# ImageSignalProcessor.net
KiCad netlist of a schematic drawn in Altium Designer
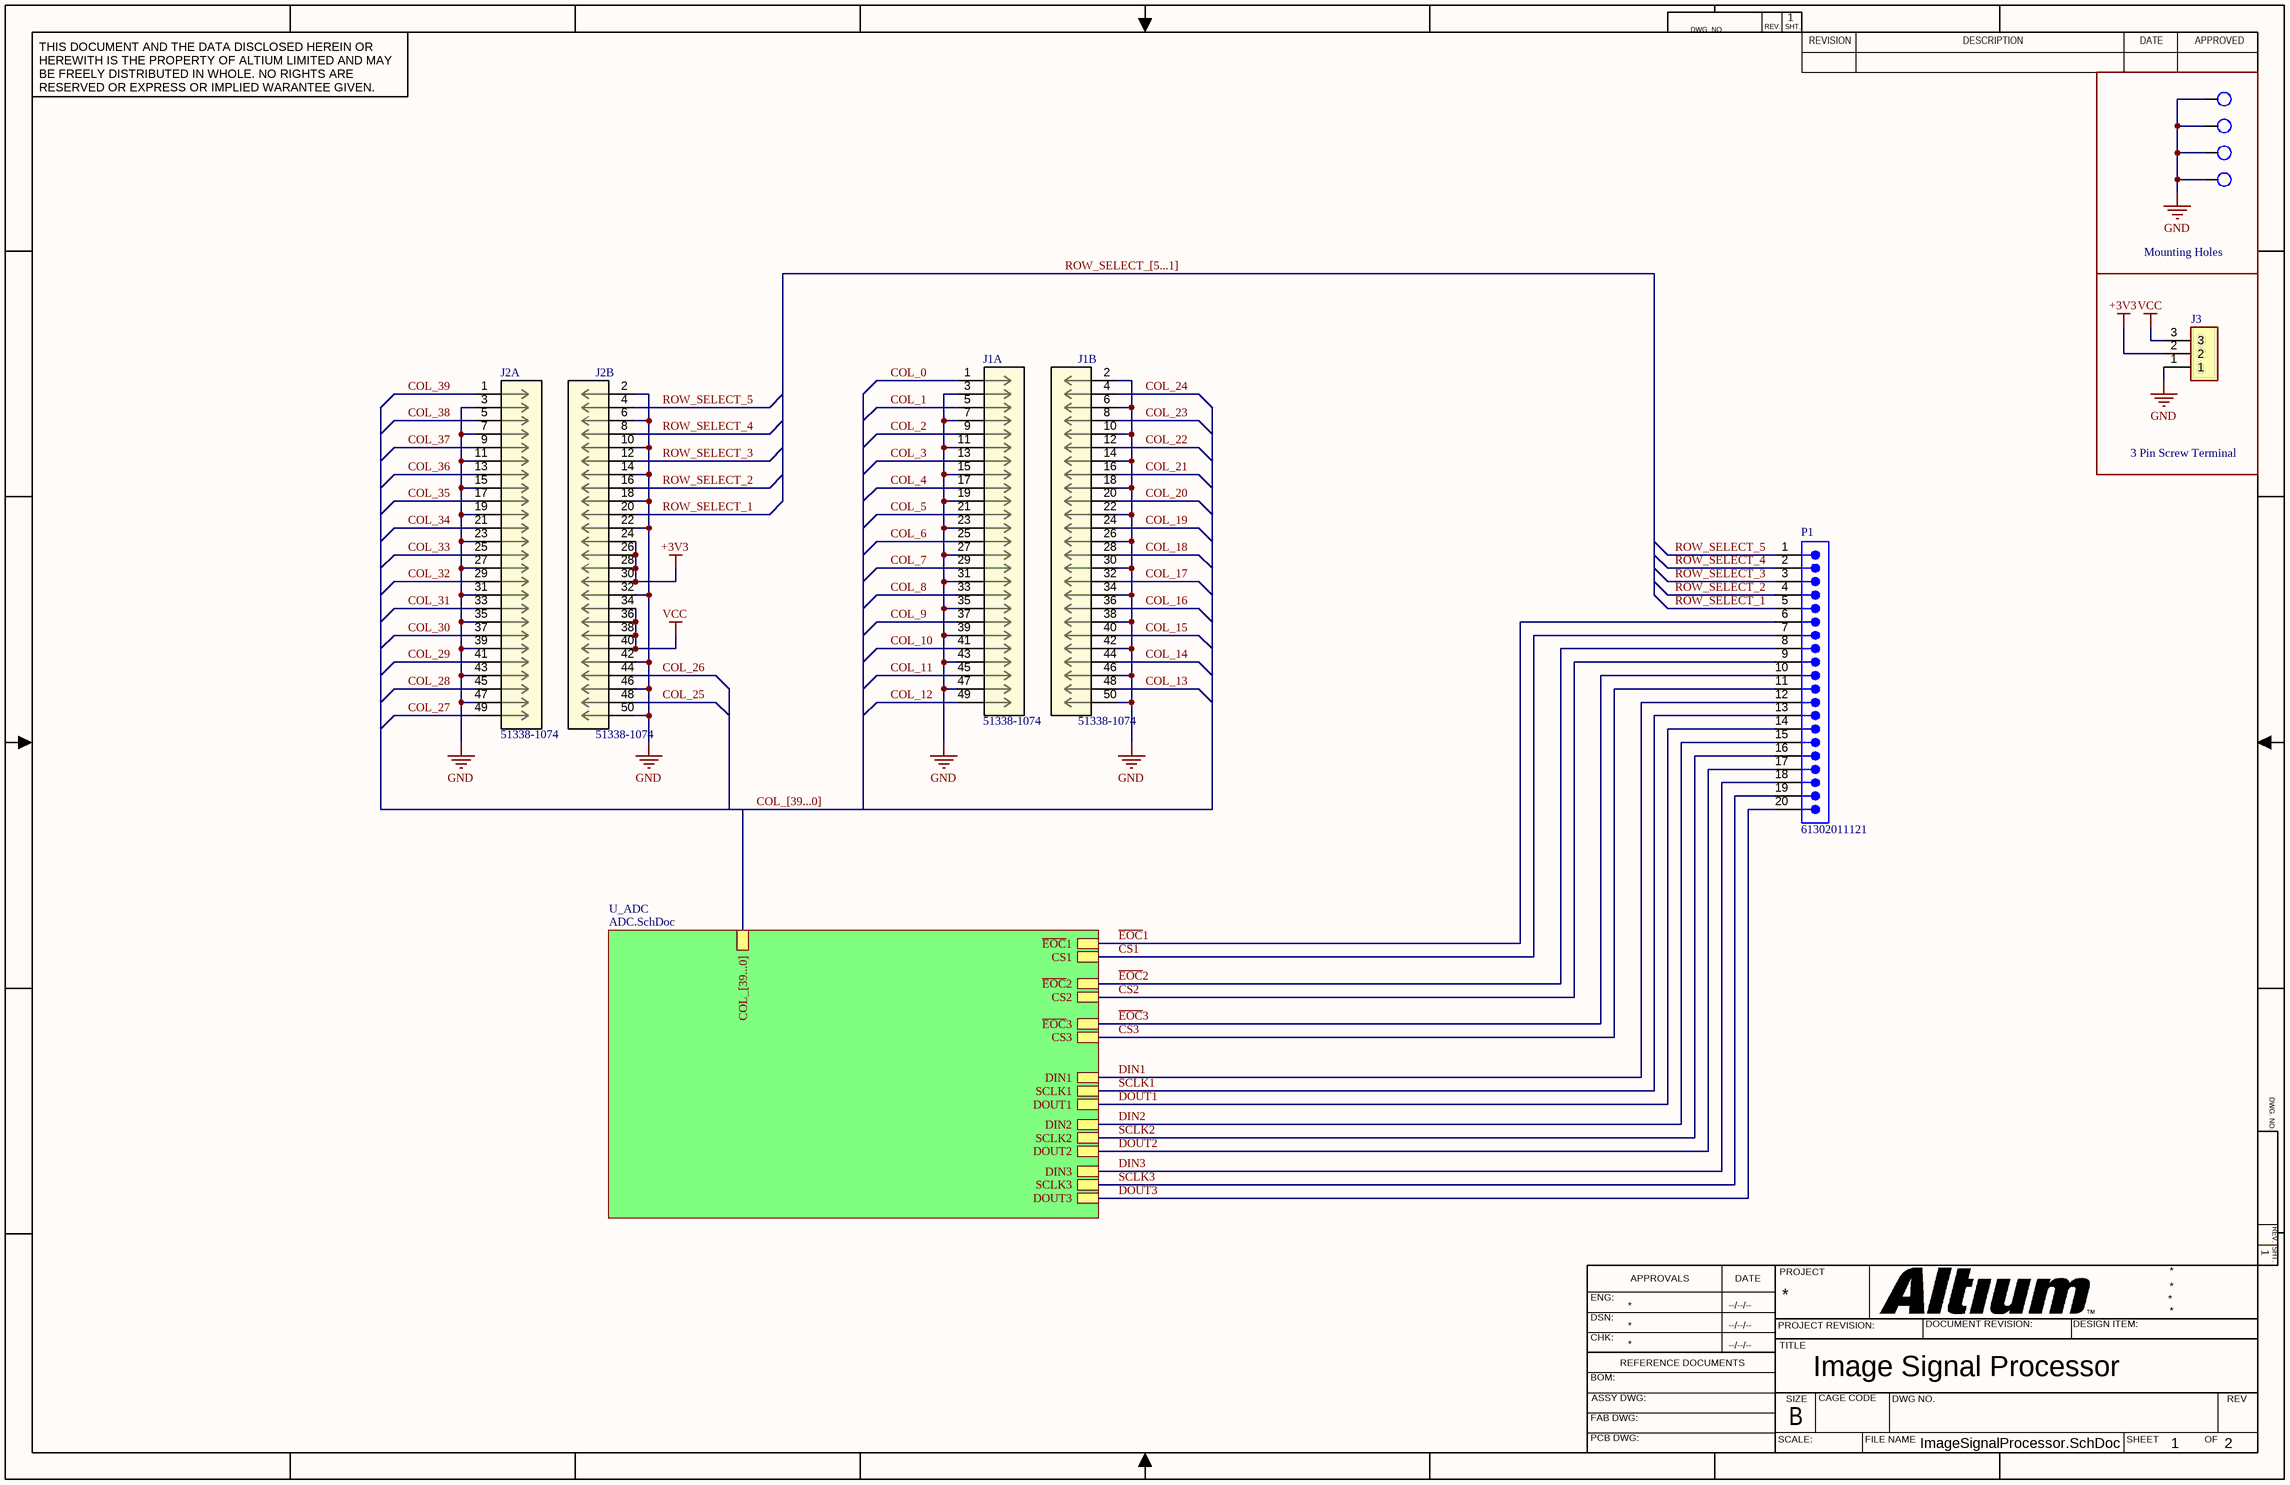
[diagram p0: ImageSignalProcessor.SchDoc]

(export (version "E")
  (design (tool "Eeschema 10.0.6"))
  (components
    (comp (ref "J1")
      (value "51338-1074")
      (footprint "51338-1074")
      (fields (field (name "MANUFACTURER") "Molex"))
      (libsource (lib "NeoObscura") (part "51338-1074"))
    )
    (comp (ref "J2")
      (value "51338-1074")
      (footprint "51338-1074")
      (fields (field (name "MANUFACTURER") "Molex"))
      (libsource (lib "NeoObscura") (part "51338-1074"))
    )
    (comp (ref "J3")
      (value "3 Pin Screw Terminal")
      (footprint "TE_282837-3")
      (description "Modular Terminal Block, 13.5A, 1.5mm2, 1 Row(s), 1 Deck(s)")
      (fields
        (field (name "MANUFACTURER") "TE Connectivity")
        (field (name "MANUFACTURER PART NUMBER") "282837-3")
        (field (name "SAFETY APPROVAL") "UL")
      )
      (libsource (lib "NeoObscura") (part "282837-3"))
    )
    (comp (ref "MP1")
      (value "M3 MOUNTING HOLE")
      (footprint "M3 MOUNTING HOLE")
      (libsource (lib "NeoObscura") (part "M3 MOUNTING HOLE"))
    )
    (comp (ref "MP2")
      (value "M3 MOUNTING HOLE")
      (footprint "M3 MOUNTING HOLE")
      (libsource (lib "NeoObscura") (part "M3 MOUNTING HOLE"))
    )
    (comp (ref "MP3")
      (value "M3 MOUNTING HOLE")
      (footprint "M3 MOUNTING HOLE")
      (libsource (lib "NeoObscura") (part "M3 MOUNTING HOLE"))
    )
    (comp (ref "MP4")
      (value "M3 MOUNTING HOLE")
      (footprint "M3 MOUNTING HOLE")
      (libsource (lib "NeoObscura") (part "M3 MOUNTING HOLE"))
    )
    (comp (ref "P1")
      (value "61302011121")
      (footprint "61302011121")
      (libsource (lib "Altium Content Vault") (part "Header_Male_1R_20P"))
    )
  )
  (nets
    (net (code "3") (name "+3V3") (class "Default")
      (node (ref "J2") (pin "24") (pinfunction "24_24") (pintype "passive"))
      (node (ref "J2") (pin "26") (pinfunction "26_26") (pintype "passive"))
      (node (ref "J2") (pin "28") (pinfunction "28_28") (pintype "passive"))
      (node (ref "J2") (pin "30") (pinfunction "30_30") (pintype "passive"))
      (node (ref "J3") (pin "2") (pinfunction "2_2") (pintype "passive"))
    )
    (net (code "4") (name "/COL_0") (class "Default")
      (node (ref "J1") (pin "1") (pinfunction "1_1") (pintype "passive"))
    )
    (net (code "5") (name "/COL_1") (class "Default")
      (node (ref "J1") (pin "5") (pinfunction "5_5") (pintype "passive"))
    )
    (net (code "6") (name "/COL_2") (class "Default")
      (node (ref "J1") (pin "9") (pinfunction "9_9") (pintype "passive"))
    )
    (net (code "7") (name "/COL_3") (class "Default")
      (node (ref "J1") (pin "13") (pinfunction "13_13") (pintype "passive"))
    )
    (net (code "8") (name "/COL_4") (class "Default")
      (node (ref "J1") (pin "17") (pinfunction "17_17") (pintype "passive"))
    )
    (net (code "9") (name "/COL_5") (class "Default")
      (node (ref "J1") (pin "21") (pinfunction "21_21") (pintype "passive"))
    )
    (net (code "10") (name "/COL_6") (class "Default")
      (node (ref "J1") (pin "25") (pinfunction "25_25") (pintype "passive"))
    )
    (net (code "11") (name "/COL_7") (class "Default")
      (node (ref "J1") (pin "29") (pinfunction "29_29") (pintype "passive"))
    )
    (net (code "12") (name "/COL_8") (class "Default")
      (node (ref "J1") (pin "33") (pinfunction "33_33") (pintype "passive"))
    )
    (net (code "13") (name "/COL_9") (class "Default")
      (node (ref "J1") (pin "37") (pinfunction "37_37") (pintype "passive"))
    )
    (net (code "14") (name "/COL_10") (class "Default")
      (node (ref "J1") (pin "41") (pinfunction "41_41") (pintype "passive"))
    )
    (net (code "15") (name "/COL_11") (class "Default")
      (node (ref "J1") (pin "45") (pinfunction "45_45") (pintype "passive"))
    )
    (net (code "16") (name "/COL_12") (class "Default")
      (node (ref "J1") (pin "49") (pinfunction "49_49") (pintype "passive"))
    )
    (net (code "17") (name "/COL_13") (class "Default")
      (node (ref "J1") (pin "48") (pinfunction "48_48") (pintype "passive"))
    )
    (net (code "18") (name "/COL_14") (class "Default")
      (node (ref "J1") (pin "44") (pinfunction "44_44") (pintype "passive"))
    )
    (net (code "19") (name "/COL_15") (class "Default")
      (node (ref "J1") (pin "40") (pinfunction "40_40") (pintype "passive"))
    )
    (net (code "20") (name "/COL_16") (class "Default")
      (node (ref "J1") (pin "36") (pinfunction "36_36") (pintype "passive"))
    )
    (net (code "21") (name "/COL_17") (class "Default")
      (node (ref "J1") (pin "32") (pinfunction "32_32") (pintype "passive"))
    )
    (net (code "22") (name "/COL_18") (class "Default")
      (node (ref "J1") (pin "28") (pinfunction "28_28") (pintype "passive"))
    )
    (net (code "23") (name "/COL_19") (class "Default")
      (node (ref "J1") (pin "24") (pinfunction "24_24") (pintype "passive"))
    )
    (net (code "24") (name "/COL_20") (class "Default")
      (node (ref "J1") (pin "20") (pinfunction "20_20") (pintype "passive"))
    )
    (net (code "25") (name "/COL_21") (class "Default")
      (node (ref "J1") (pin "16") (pinfunction "16_16") (pintype "passive"))
    )
    (net (code "26") (name "/COL_22") (class "Default")
      (node (ref "J1") (pin "12") (pinfunction "12_12") (pintype "passive"))
    )
    (net (code "27") (name "/COL_23") (class "Default")
      (node (ref "J1") (pin "8") (pinfunction "8_8") (pintype "passive"))
    )
    (net (code "28") (name "/COL_24") (class "Default")
      (node (ref "J1") (pin "4") (pinfunction "4_4") (pintype "passive"))
    )
    (net (code "29") (name "/COL_25") (class "Default")
      (node (ref "J2") (pin "48") (pinfunction "48_48") (pintype "passive"))
    )
    (net (code "30") (name "/COL_26") (class "Default")
      (node (ref "J2") (pin "44") (pinfunction "44_44") (pintype "passive"))
    )
    (net (code "31") (name "/COL_27") (class "Default")
      (node (ref "J2") (pin "49") (pinfunction "49_49") (pintype "passive"))
    )
    (net (code "32") (name "/COL_28") (class "Default")
      (node (ref "J2") (pin "45") (pinfunction "45_45") (pintype "passive"))
    )
    (net (code "33") (name "/COL_29") (class "Default")
      (node (ref "J2") (pin "41") (pinfunction "41_41") (pintype "passive"))
    )
    (net (code "34") (name "/COL_30") (class "Default")
      (node (ref "J2") (pin "37") (pinfunction "37_37") (pintype "passive"))
    )
    (net (code "35") (name "/COL_31") (class "Default")
      (node (ref "J2") (pin "33") (pinfunction "33_33") (pintype "passive"))
    )
    (net (code "36") (name "/COL_32") (class "Default")
      (node (ref "J2") (pin "29") (pinfunction "29_29") (pintype "passive"))
    )
    (net (code "37") (name "/COL_33") (class "Default")
      (node (ref "J2") (pin "25") (pinfunction "25_25") (pintype "passive"))
    )
    (net (code "38") (name "/COL_34") (class "Default")
      (node (ref "J2") (pin "21") (pinfunction "21_21") (pintype "passive"))
    )
    (net (code "39") (name "/COL_35") (class "Default")
      (node (ref "J2") (pin "17") (pinfunction "17_17") (pintype "passive"))
    )
    (net (code "40") (name "/COL_36") (class "Default")
      (node (ref "J2") (pin "13") (pinfunction "13_13") (pintype "passive"))
    )
    (net (code "41") (name "/COL_37") (class "Default")
      (node (ref "J2") (pin "9") (pinfunction "9_9") (pintype "passive"))
    )
    (net (code "42") (name "/COL_38") (class "Default")
      (node (ref "J2") (pin "5") (pinfunction "5_5") (pintype "passive"))
    )
    (net (code "43") (name "/COL_39") (class "Default")
      (node (ref "J2") (pin "1") (pinfunction "1_1") (pintype "passive"))
    )
    (net (code "44") (name "/CS1") (class "Default")
      (node (ref "P1") (pin "7") (pinfunction "7_7") (pintype "passive"))
    )
    (net (code "45") (name "/CS2") (class "Default")
      (node (ref "P1") (pin "9") (pinfunction "9_9") (pintype "passive"))
    )
    (net (code "46") (name "/CS3") (class "Default")
      (node (ref "P1") (pin "11") (pinfunction "11_11") (pintype "passive"))
    )
    (net (code "47") (name "/DIN1") (class "Default")
      (node (ref "P1") (pin "12") (pinfunction "12_12") (pintype "passive"))
    )
    (net (code "48") (name "/DIN2") (class "Default")
      (node (ref "P1") (pin "15") (pinfunction "15_15") (pintype "passive"))
    )
    (net (code "49") (name "/DIN3") (class "Default")
      (node (ref "P1") (pin "18") (pinfunction "18_18") (pintype "passive"))
    )
    (net (code "50") (name "/DOUT1") (class "Default")
      (node (ref "P1") (pin "14") (pinfunction "14_14") (pintype "passive"))
    )
    (net (code "51") (name "/DOUT2") (class "Default")
      (node (ref "P1") (pin "17") (pinfunction "17_17") (pintype "passive"))
    )
    (net (code "52") (name "/DOUT3") (class "Default")
      (node (ref "P1") (pin "20") (pinfunction "20_20") (pintype "passive"))
    )
    (net (code "53") (name "/ROW_SELECT_1") (class "Default")
      (node (ref "J2") (pin "20") (pinfunction "20_20") (pintype "passive"))
      (node (ref "P1") (pin "5") (pinfunction "5_5") (pintype "passive"))
    )
    (net (code "54") (name "/ROW_SELECT_2") (class "Default")
      (node (ref "J2") (pin "16") (pinfunction "16_16") (pintype "passive"))
      (node (ref "P1") (pin "4") (pinfunction "4_4") (pintype "passive"))
    )
    (net (code "55") (name "/ROW_SELECT_3") (class "Default")
      (node (ref "J2") (pin "12") (pinfunction "12_12") (pintype "passive"))
      (node (ref "P1") (pin "3") (pinfunction "3_3") (pintype "passive"))
    )
    (net (code "56") (name "/ROW_SELECT_4") (class "Default")
      (node (ref "J2") (pin "8") (pinfunction "8_8") (pintype "passive"))
      (node (ref "P1") (pin "2") (pinfunction "2_2") (pintype "passive"))
    )
    (net (code "57") (name "/ROW_SELECT_5") (class "Default")
      (node (ref "J2") (pin "4") (pinfunction "4_4") (pintype "passive"))
      (node (ref "P1") (pin "1") (pinfunction "1_1") (pintype "passive"))
    )
    (net (code "58") (name "/SCLK1") (class "Default")
      (node (ref "P1") (pin "13") (pinfunction "13_13") (pintype "passive"))
    )
    (net (code "59") (name "/SCLK2") (class "Default")
      (node (ref "P1") (pin "16") (pinfunction "16_16") (pintype "passive"))
    )
    (net (code "60") (name "/SCLK3") (class "Default")
      (node (ref "P1") (pin "19") (pinfunction "19_19") (pintype "passive"))
    )
    (net (code "63") (name "/~{EOC}1") (class "Default")
      (node (ref "P1") (pin "6") (pinfunction "6_6") (pintype "passive"))
    )
    (net (code "64") (name "/~{EOC}2") (class "Default")
      (node (ref "P1") (pin "8") (pinfunction "8_8") (pintype "passive"))
    )
    (net (code "65") (name "/~{EOC}3") (class "Default")
      (node (ref "P1") (pin "10") (pinfunction "10_10") (pintype "passive"))
    )
    (net (code "66") (name "GND") (class "Default")
      (node (ref "J1") (pin "10") (pinfunction "10_10") (pintype "passive"))
      (node (ref "J1") (pin "11") (pinfunction "11_11") (pintype "passive"))
      (node (ref "J1") (pin "14") (pinfunction "14_14") (pintype "passive"))
      (node (ref "J1") (pin "15") (pinfunction "15_15") (pintype "passive"))
      (node (ref "J1") (pin "18") (pinfunction "18_18") (pintype "passive"))
      (node (ref "J1") (pin "19") (pinfunction "19_19") (pintype "passive"))
      (node (ref "J1") (pin "2") (pinfunction "2_2") (pintype "passive"))
      (node (ref "J1") (pin "22") (pinfunction "22_22") (pintype "passive"))
      (node (ref "J1") (pin "23") (pinfunction "23_23") (pintype "passive"))
      (node (ref "J1") (pin "26") (pinfunction "26_26") (pintype "passive"))
      (node (ref "J1") (pin "27") (pinfunction "27_27") (pintype "passive"))
      (node (ref "J1") (pin "3") (pinfunction "3_3") (pintype "passive"))
      (node (ref "J1") (pin "30") (pinfunction "30_30") (pintype "passive"))
      (node (ref "J1") (pin "31") (pinfunction "31_31") (pintype "passive"))
      (node (ref "J1") (pin "34") (pinfunction "34_34") (pintype "passive"))
      (node (ref "J1") (pin "35") (pinfunction "35_35") (pintype "passive"))
      (node (ref "J1") (pin "38") (pinfunction "38_38") (pintype "passive"))
      (node (ref "J1") (pin "39") (pinfunction "39_39") (pintype "passive"))
      (node (ref "J1") (pin "42") (pinfunction "42_42") (pintype "passive"))
      (node (ref "J1") (pin "43") (pinfunction "43_43") (pintype "passive"))
      (node (ref "J1") (pin "46") (pinfunction "46_46") (pintype "passive"))
      (node (ref "J1") (pin "47") (pinfunction "47_47") (pintype "passive"))
      (node (ref "J1") (pin "50") (pinfunction "50_50") (pintype "passive"))
      (node (ref "J1") (pin "6") (pinfunction "6_6") (pintype "passive"))
      (node (ref "J1") (pin "7") (pinfunction "7_7") (pintype "passive"))
      (node (ref "J2") (pin "10") (pinfunction "10_10") (pintype "passive"))
      (node (ref "J2") (pin "11") (pinfunction "11_11") (pintype "passive"))
      (node (ref "J2") (pin "14") (pinfunction "14_14") (pintype "passive"))
      (node (ref "J2") (pin "15") (pinfunction "15_15") (pintype "passive"))
      (node (ref "J2") (pin "18") (pinfunction "18_18") (pintype "passive"))
      (node (ref "J2") (pin "19") (pinfunction "19_19") (pintype "passive"))
      (node (ref "J2") (pin "2") (pinfunction "2_2") (pintype "passive"))
      (node (ref "J2") (pin "22") (pinfunction "22_22") (pintype "passive"))
      (node (ref "J2") (pin "23") (pinfunction "23_23") (pintype "passive"))
      (node (ref "J2") (pin "27") (pinfunction "27_27") (pintype "passive"))
      (node (ref "J2") (pin "3") (pinfunction "3_3") (pintype "passive"))
      (node (ref "J2") (pin "31") (pinfunction "31_31") (pintype "passive"))
      (node (ref "J2") (pin "32") (pinfunction "32_32") (pintype "passive"))
      (node (ref "J2") (pin "35") (pinfunction "35_35") (pintype "passive"))
      (node (ref "J2") (pin "39") (pinfunction "39_39") (pintype "passive"))
      (node (ref "J2") (pin "42") (pinfunction "42_42") (pintype "passive"))
      (node (ref "J2") (pin "43") (pinfunction "43_43") (pintype "passive"))
      (node (ref "J2") (pin "46") (pinfunction "46_46") (pintype "passive"))
      (node (ref "J2") (pin "47") (pinfunction "47_47") (pintype "passive"))
      (node (ref "J2") (pin "50") (pinfunction "50_50") (pintype "passive"))
      (node (ref "J2") (pin "6") (pinfunction "6_6") (pintype "passive"))
      (node (ref "J2") (pin "7") (pinfunction "7_7") (pintype "passive"))
      (node (ref "J3") (pin "1") (pinfunction "1_1") (pintype "passive"))
      (node (ref "MP1") (pin "1") (pinfunction "1_1") (pintype "passive"))
      (node (ref "MP2") (pin "1") (pinfunction "1_1") (pintype "passive"))
      (node (ref "MP3") (pin "1") (pinfunction "1_1") (pintype "passive"))
      (node (ref "MP4") (pin "1") (pinfunction "1_1") (pintype "passive"))
    )
    (net (code "67") (name "VCC") (class "Default")
      (node (ref "J2") (pin "34") (pinfunction "34_34") (pintype "passive"))
      (node (ref "J2") (pin "36") (pinfunction "36_36") (pintype "passive"))
      (node (ref "J2") (pin "38") (pinfunction "38_38") (pintype "passive"))
      (node (ref "J2") (pin "40") (pinfunction "40_40") (pintype "passive"))
      (node (ref "J3") (pin "3") (pinfunction "3_3") (pintype "passive"))
    )
  )
)
